# 467444_130_3_4-A.net
KiCad netlist of a schematic drawn in Altium Designer
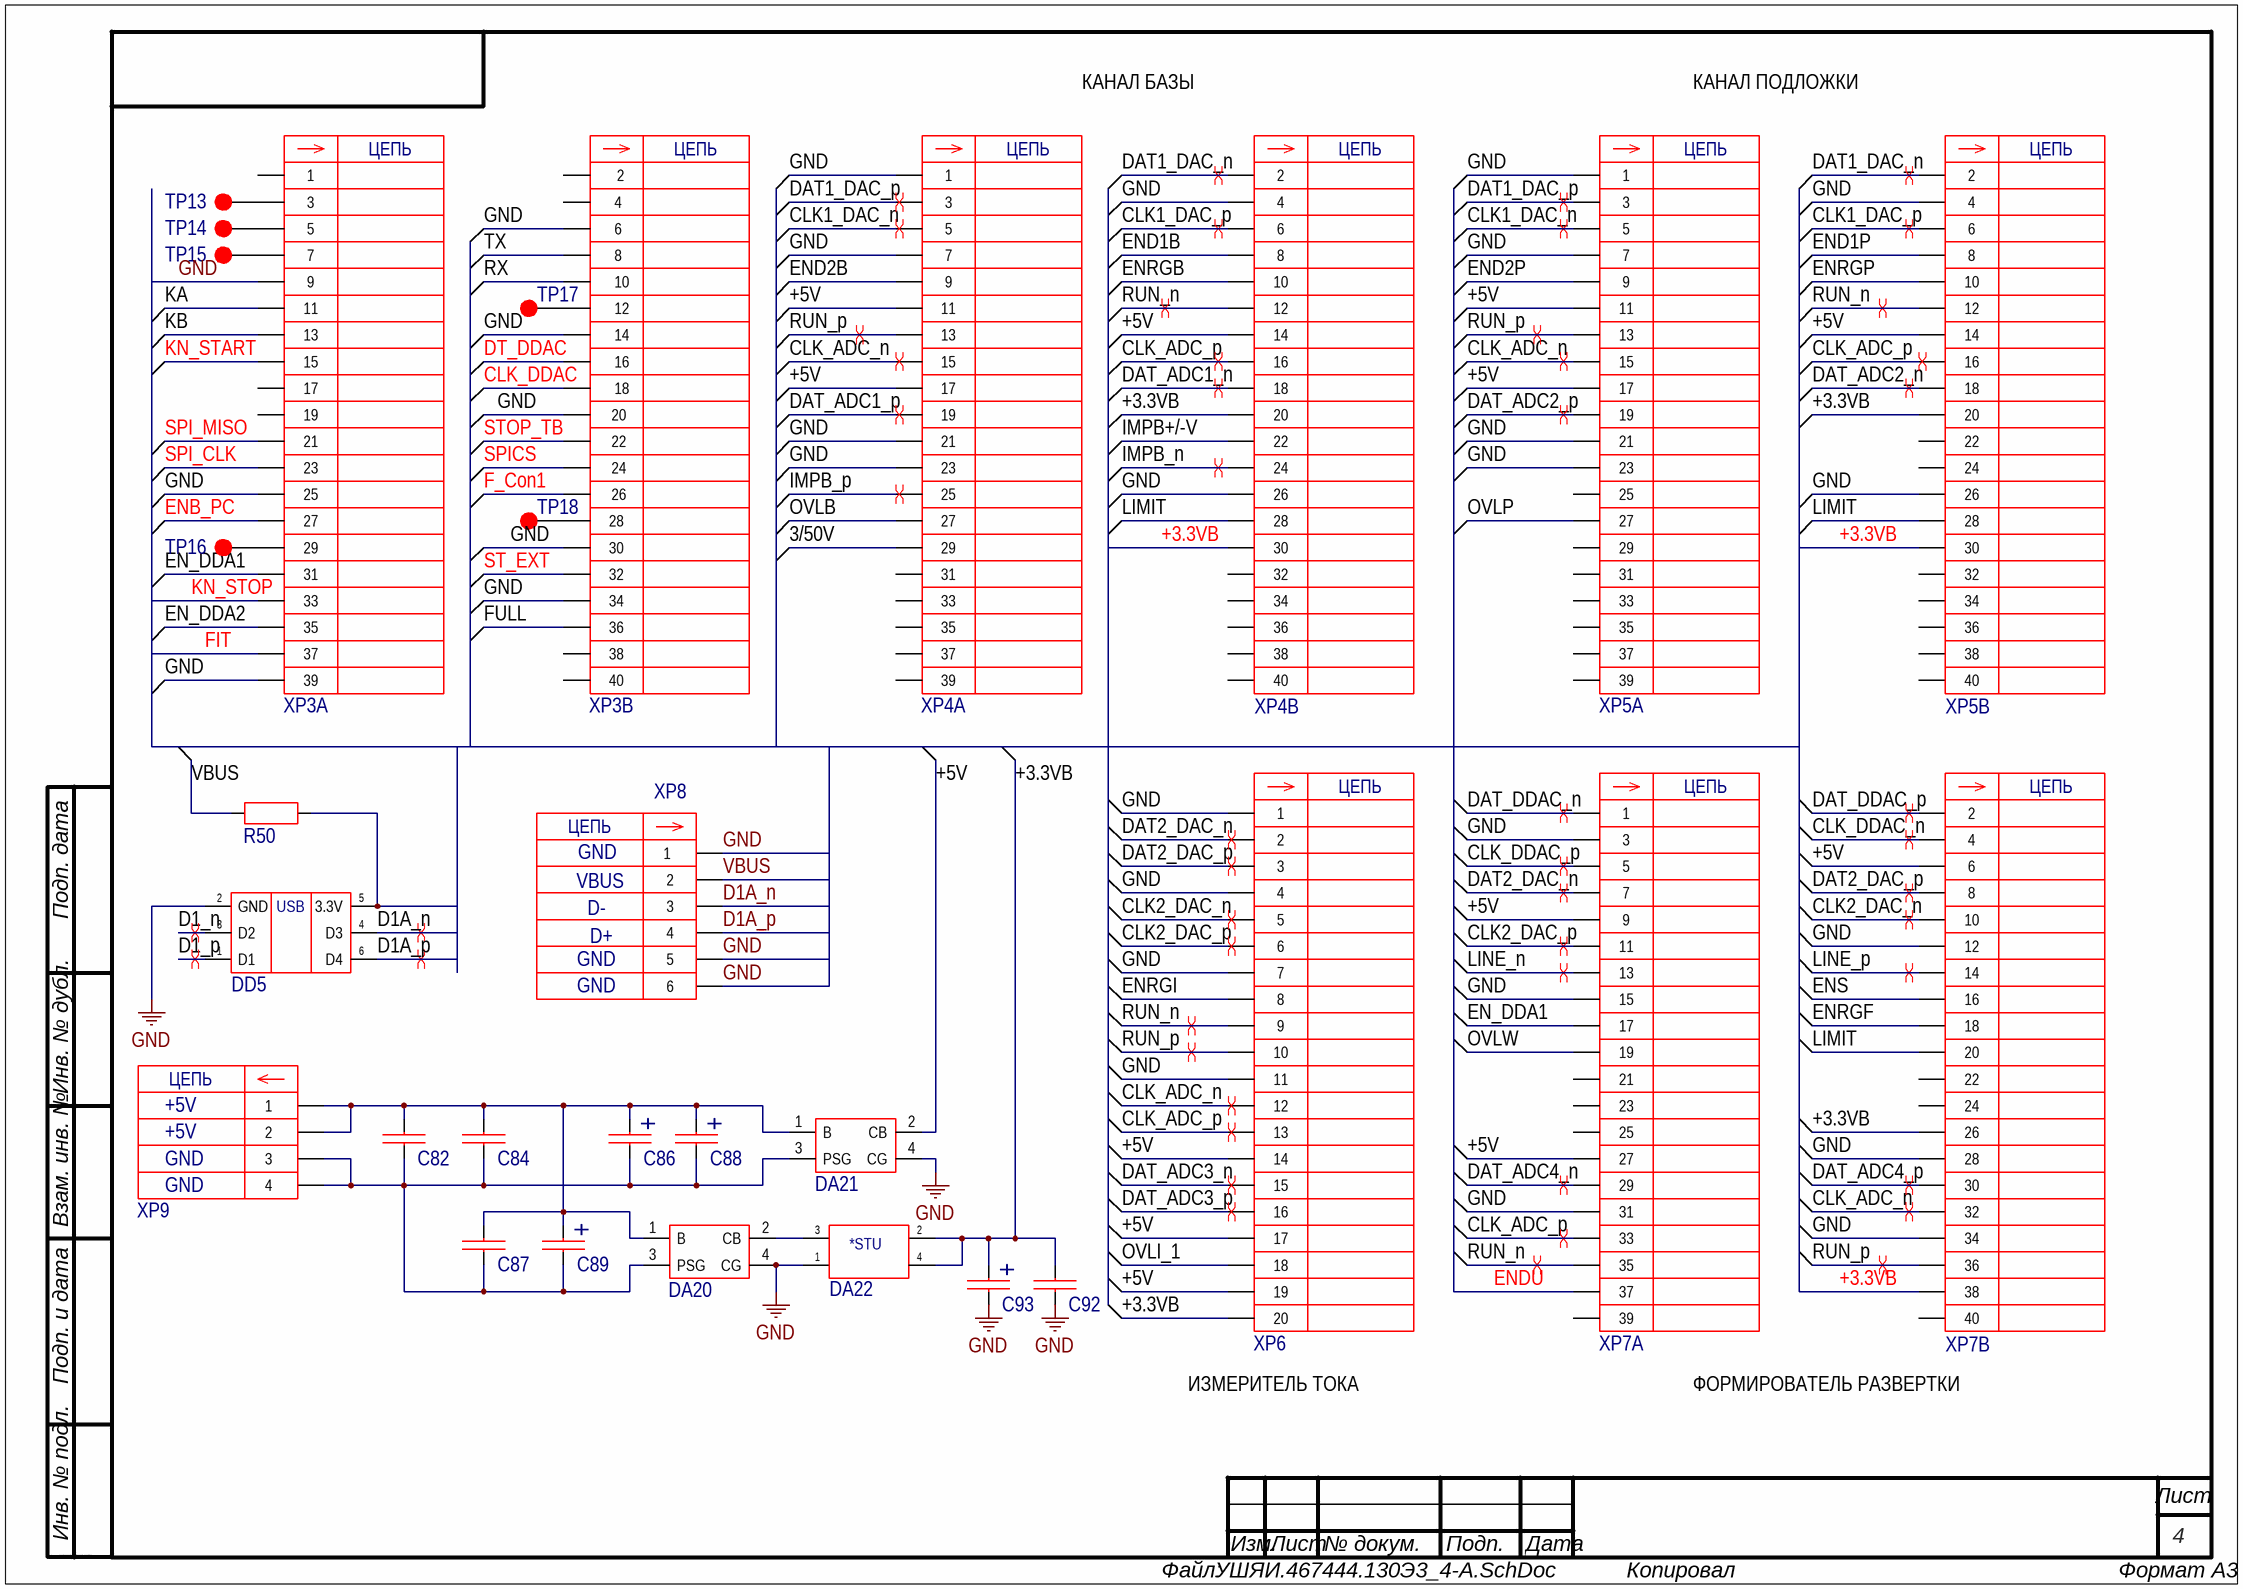
[diagram p0: УШЯИ.467444.130Э3_4-A.SchDoc]

(export (version "E")
  (design (tool "Eeschema 10.0.6"))
  (components
    (comp (ref "C82")
      (value "0,1 µF")
      (footprint "C_0805 [2012 Metric]")
      (description "Неполярный конденсатор")
      (fields (field (name "MANUFACTURER") "Murata") (field (name "VOLTAGE") "50V"))
      (libsource (lib "lib") (part "C_const"))
    )
    (comp (ref "C84")
      (value "0,1 µF")
      (footprint "C_0805 [2012 Metric]")
      (description "Неполярный конденсатор")
      (fields (field (name "MANUFACTURER") "Murata") (field (name "VOLTAGE") "50V"))
      (libsource (lib "lib") (part "C_const"))
    )
    (comp (ref "C86")
      (value "1000 µF")
      (footprint "С_EXR_10x21")
      (description "Полярный конденсатор")
      (fields (field (name "MANUFACTURER") "Hitano") (field (name "VOLTAGE") "16V"))
      (libsource (lib "lib") (part "C_electrolytic"))
    )
    (comp (ref "C87")
      (value "0,1 µF")
      (footprint "C_0805 [2012 Metric]")
      (description "Неполярный конденсатор")
      (fields (field (name "MANUFACTURER") "Murata") (field (name "VOLTAGE") "50V"))
      (libsource (lib "lib") (part "C_const"))
    )
    (comp (ref "C88")
      (value "10 µF")
      (footprint "C+_1210 [3528-21 Metric]")
      (description "Полярный конденсатор")
      (fields (field (name "MANUFACTURER") "KYOCERA AVX") (field (name "VOLTAGE") "20V\r\n10V"))
      (libsource (lib "lib") (part "C_electrolytic"))
    )
    (comp (ref "C89")
      (value "10 µF")
      (footprint "C+_1210 [3528-21 Metric]")
      (description "Полярный конденсатор")
      (fields (field (name "MANUFACTURER") "KYOCERA AVX") (field (name "VOLTAGE") "20V\r\n10V"))
      (libsource (lib "lib") (part "C_electrolytic"))
    )
    (comp (ref "C92")
      (value "0,1 µF")
      (footprint "C_0805 [2012 Metric]")
      (description "Неполярный конденсатор")
      (fields (field (name "MANUFACTURER") "Murata") (field (name "VOLTAGE") "50V"))
      (libsource (lib "lib") (part "C_const"))
    )
    (comp (ref "C93")
      (value "10 µF")
      (footprint "C+_1210 [3528-21 Metric]")
      (description "Полярный конденсатор")
      (fields (field (name "MANUFACTURER") "KYOCERA AVX") (field (name "VOLTAGE") "20V\r\n10V"))
      (libsource (lib "lib") (part "C_electrolytic"))
    )
    (comp (ref "DA20")
      (value "BNX028-01")
      (footprint "F_BNX028-01")
      (description "16В, 35дБ")
      (fields (field (name "MANUFACTURER") "Murata Electronics"))
      (libsource (lib "lib") (part "F_BNX022-01"))
    )
    (comp (ref "DA21")
      (value "BNX028-01")
      (footprint "F_BNX028-01")
      (description "16В, 35дБ")
      (fields (field (name "MANUFACTURER") "Murata Electronics"))
      (libsource (lib "lib") (part "F_BNX022-01"))
    )
    (comp (ref "DA22")
      (value "LD1117AS33TR")
      (footprint "SOT-223")
      (description "IC, Fixed LDO Voltage Regulator, 5.3V to 10V, 1.15V Dropout, 3.3Vout, 1Aout")
      (fields (field (name "MANUFACTURER") "STMicroelectronics"))
      (libsource (lib "lib") (part "VolReg_LD1117AS33TR"))
    )
    (comp (ref "DD5")
      (value "USBUF01W6")
      (footprint "SOT-323-6")
      (description "EMI Filter, 2-Channel, USB Upstream Terminator, ESD Protection")
      (fields (field (name "MANUFACTURER") "STMicroelectronics"))
      (libsource (lib "lib") (part "USBUF01W6"))
    )
    (comp (ref "R50")
      (value "30R")
      (footprint "R_0805 [2012 Metric]")
      (fields (field (name "TOLERANCE") "±5%"))
      (libsource (lib "lib") (part "R_Const"))
    )
    (comp (ref "TP13") (value "~") (footprint "DSP_1.3") (libsource (lib "lib") (part "TP")))
    (comp (ref "TP14") (value "~") (footprint "DSP_1.3") (libsource (lib "lib") (part "TP")))
    (comp (ref "TP15") (value "~") (footprint "DSP_1.3") (libsource (lib "lib") (part "TP")))
    (comp (ref "TP16") (value "~") (footprint "DSP_1.3") (libsource (lib "lib") (part "TP")))
    (comp (ref "TP17") (value "~") (footprint "DSP_1.3") (libsource (lib "lib") (part "TP")))
    (comp (ref "TP18") (value "~") (footprint "DSP_1.3") (libsource (lib "lib") (part "TP")))
    (comp (ref "XP3")
      (value "BH-40")
      (footprint "BH-40")
      (description "Male, 40 pins, 2 rows, Vertical")
      (fields (field (name "MANUFACTURER") "Connfly electronic"))
      (libsource (lib "lib") (part "M_40"))
    )
    (comp (ref "XP4")
      (value "BH2-40")
      (footprint "BH2-40")
      (description "Male, 40 pins, 2 rows, Vertical, DS1014-40, 2 mm")
      (fields (field (name "MANUFACTURER") "Connfly electronic"))
      (libsource (lib "lib") (part "M_40"))
    )
    (comp (ref "XP5")
      (value "BH2-40")
      (footprint "BH2-40")
      (description "Male, 40 pins, 2 rows, Vertical, DS1014-40, 2 mm")
      (fields (field (name "MANUFACTURER") "Connfly electronic"))
      (libsource (lib "lib") (part "M_40"))
    )
    (comp (ref "XP6")
      (value "BH2-20R")
      (footprint "BH2-20R")
      (description "Male, 20 pins, 2 rows, Right Angle, DS1014-20RF1B-B, 2 mm")
      (fields (field (name "MANUFACTURER") "Connfly electronic"))
      (libsource (lib "lib") (part "M_20"))
    )
    (comp (ref "XP7")
      (value "BH2-40")
      (footprint "BH2-40")
      (description "Male, 40 pins, 2 rows, Vertical, DS1014-40, 2 mm")
      (fields (field (name "MANUFACTURER") "Connfly electronic"))
      (libsource (lib "lib") (part "M_40"))
    )
    (comp (ref "XP8")
      (value "AMPMODU II 280372-2")
      (footprint "AMP II-280372-2")
      (description "Male, 6 pin, 1 row, Vertical, Board-to-Board, 2.54 mm")
      (fields (field (name "MANUFACTURER") "TE Connectivity"))
      (libsource (lib "Lib_MN") (part "M_6"))
    )
    (comp (ref "XP9")
      (value "AMPMODU II 280371-2")
      (footprint "AMP II-280371-2")
      (description "Male, 4 pin, 1 row, Vertical, Board-to-Board, 2.54 mm")
      (fields (field (name "MANUFACTURER") "TE Connectivity"))
      (libsource (lib "lib") (part "M_4"))
    )
  )
  (nets
    (net (code "1") (name "/+3.3VB") (class "Default")
      (node (ref "C92") (pin "2") (pinfunction "2_2") (pintype "passive"))
      (node (ref "C93") (pin "+") (pinfunction "+_+") (pintype "passive"))
      (node (ref "DA22") (pin "2") (pinfunction "VOUT_2") (pintype "passive"))
      (node (ref "DA22") (pin "4") (pinfunction "VOUT_4") (pintype "passive"))
      (node (ref "XP4") (pin "20") (pinfunction "20_20") (pintype "passive"))
      (node (ref "XP4") (pin "30") (pinfunction "30_30") (pintype "passive"))
      (node (ref "XP5") (pin "20") (pinfunction "20_20") (pintype "passive"))
      (node (ref "XP5") (pin "30") (pinfunction "30_30") (pintype "passive"))
      (node (ref "XP6") (pin "20") (pinfunction "20_20") (pintype "passive"))
      (node (ref "XP7") (pin "26") (pinfunction "26_26") (pintype "passive"))
      (node (ref "XP7") (pin "38") (pinfunction "38_38") (pintype "passive"))
    )
    (net (code "2") (name "/+5V") (class "Default")
      (node (ref "DA21") (pin "2") (pinfunction "CB_2") (pintype "passive"))
      (node (ref "XP4") (pin "11") (pinfunction "11_11") (pintype "passive"))
      (node (ref "XP4") (pin "14") (pinfunction "14_14") (pintype "passive"))
      (node (ref "XP4") (pin "17") (pinfunction "17_17") (pintype "passive"))
      (node (ref "XP5") (pin "11") (pinfunction "11_11") (pintype "passive"))
      (node (ref "XP5") (pin "14") (pinfunction "14_14") (pintype "passive"))
      (node (ref "XP5") (pin "17") (pinfunction "17_17") (pintype "passive"))
      (node (ref "XP6") (pin "14") (pinfunction "14_14") (pintype "passive"))
      (node (ref "XP6") (pin "17") (pinfunction "17_17") (pintype "passive"))
      (node (ref "XP6") (pin "19") (pinfunction "19_19") (pintype "passive"))
      (node (ref "XP7") (pin "27") (pinfunction "27_27") (pintype "passive"))
      (node (ref "XP7") (pin "6") (pinfunction "6_6") (pintype "passive"))
      (node (ref "XP7") (pin "9") (pinfunction "9_9") (pintype "passive"))
    )
    (net (code "3") (name "/3{slash}50V") (class "Default")
      (node (ref "XP4") (pin "29") (pinfunction "29_29") (pintype "passive"))
    )
    (net (code "4") (name "/CLK1_DAC_n") (class "Default")
      (node (ref "XP4") (pin "5") (pinfunction "5_5") (pintype "passive"))
      (node (ref "XP5") (pin "5") (pinfunction "5_5") (pintype "passive"))
    )
    (net (code "5") (name "/CLK1_DAC_p") (class "Default")
      (node (ref "XP4") (pin "6") (pinfunction "6_6") (pintype "passive"))
      (node (ref "XP5") (pin "6") (pinfunction "6_6") (pintype "passive"))
    )
    (net (code "6") (name "/CLK2_DAC_n") (class "Default")
      (node (ref "XP6") (pin "5") (pinfunction "5_5") (pintype "passive"))
      (node (ref "XP7") (pin "10") (pinfunction "10_10") (pintype "passive"))
    )
    (net (code "7") (name "/CLK2_DAC_p") (class "Default")
      (node (ref "XP6") (pin "6") (pinfunction "6_6") (pintype "passive"))
      (node (ref "XP7") (pin "11") (pinfunction "11_11") (pintype "passive"))
    )
    (net (code "8") (name "/CLK_ADC_n") (class "Default")
      (node (ref "XP4") (pin "15") (pinfunction "15_15") (pintype "passive"))
      (node (ref "XP5") (pin "15") (pinfunction "15_15") (pintype "passive"))
      (node (ref "XP6") (pin "12") (pinfunction "12_12") (pintype "passive"))
      (node (ref "XP7") (pin "32") (pinfunction "32_32") (pintype "passive"))
    )
    (net (code "9") (name "/CLK_ADC_p") (class "Default")
      (node (ref "XP4") (pin "16") (pinfunction "16_16") (pintype "passive"))
      (node (ref "XP5") (pin "16") (pinfunction "16_16") (pintype "passive"))
      (node (ref "XP6") (pin "13") (pinfunction "13_13") (pintype "passive"))
      (node (ref "XP7") (pin "33") (pinfunction "33_33") (pintype "passive"))
    )
    (net (code "10") (name "/CLK_DDAC") (class "Default")
      (node (ref "XP3") (pin "18") (pinfunction "18_18") (pintype "passive"))
    )
    (net (code "11") (name "/CLK_DDAC_n") (class "Default")
      (node (ref "XP7") (pin "4") (pinfunction "4_4") (pintype "passive"))
    )
    (net (code "12") (name "/CLK_DDAC_p") (class "Default")
      (node (ref "XP7") (pin "5") (pinfunction "5_5") (pintype "passive"))
    )
    (net (code "13") (name "/D1A_n") (class "Default")
      (node (ref "DD5") (pin "4") (pinfunction "D3_4") (pintype "passive"))
      (node (ref "XP8") (pin "3") (pinfunction "3_3") (pintype "passive"))
    )
    (net (code "14") (name "/D1A_p") (class "Default")
      (node (ref "DD5") (pin "6") (pinfunction "D4_6") (pintype "passive"))
      (node (ref "XP8") (pin "4") (pinfunction "4_4") (pintype "passive"))
    )
    (net (code "15") (name "/D1_n") (class "Default")
      (node (ref "DD5") (pin "3") (pinfunction "D2_3") (pintype "passive"))
    )
    (net (code "16") (name "/D1_p") (class "Default")
      (node (ref "DD5") (pin "1") (pinfunction "D1_1") (pintype "passive"))
    )
    (net (code "17") (name "/DAT1_DAC_n") (class "Default")
      (node (ref "XP4") (pin "2") (pinfunction "2_2") (pintype "passive"))
      (node (ref "XP5") (pin "2") (pinfunction "2_2") (pintype "passive"))
    )
    (net (code "18") (name "/DAT1_DAC_p") (class "Default")
      (node (ref "XP4") (pin "3") (pinfunction "3_3") (pintype "passive"))
      (node (ref "XP5") (pin "3") (pinfunction "3_3") (pintype "passive"))
    )
    (net (code "19") (name "/DAT2_DAC_n") (class "Default")
      (node (ref "XP6") (pin "2") (pinfunction "2_2") (pintype "passive"))
      (node (ref "XP7") (pin "7") (pinfunction "7_7") (pintype "passive"))
    )
    (net (code "20") (name "/DAT2_DAC_p") (class "Default")
      (node (ref "XP6") (pin "3") (pinfunction "3_3") (pintype "passive"))
      (node (ref "XP7") (pin "8") (pinfunction "8_8") (pintype "passive"))
    )
    (net (code "21") (name "/DAT_ADC1_n") (class "Default")
      (node (ref "XP4") (pin "18") (pinfunction "18_18") (pintype "passive"))
    )
    (net (code "22") (name "/DAT_ADC1_p") (class "Default")
      (node (ref "XP4") (pin "19") (pinfunction "19_19") (pintype "passive"))
    )
    (net (code "23") (name "/DAT_ADC2_n") (class "Default")
      (node (ref "XP5") (pin "18") (pinfunction "18_18") (pintype "passive"))
    )
    (net (code "24") (name "/DAT_ADC2_p") (class "Default")
      (node (ref "XP5") (pin "19") (pinfunction "19_19") (pintype "passive"))
    )
    (net (code "25") (name "/DAT_ADC3_n") (class "Default")
      (node (ref "XP6") (pin "15") (pinfunction "15_15") (pintype "passive"))
    )
    (net (code "26") (name "/DAT_ADC3_p") (class "Default")
      (node (ref "XP6") (pin "16") (pinfunction "16_16") (pintype "passive"))
    )
    (net (code "27") (name "/DAT_ADC4_n") (class "Default")
      (node (ref "XP7") (pin "29") (pinfunction "29_29") (pintype "passive"))
    )
    (net (code "28") (name "/DAT_ADC4_p") (class "Default")
      (node (ref "XP7") (pin "30") (pinfunction "30_30") (pintype "passive"))
    )
    (net (code "29") (name "/DAT_DDAC_n") (class "Default")
      (node (ref "XP7") (pin "1") (pinfunction "1_1") (pintype "passive"))
    )
    (net (code "30") (name "/DAT_DDAC_p") (class "Default")
      (node (ref "XP7") (pin "2") (pinfunction "2_2") (pintype "passive"))
    )
    (net (code "31") (name "/DT_DDAC") (class "Default")
      (node (ref "XP3") (pin "16") (pinfunction "16_16") (pintype "passive"))
    )
    (net (code "32") (name "/ENB_PC") (class "Default")
      (node (ref "XP3") (pin "27") (pinfunction "27_27") (pintype "passive"))
    )
    (net (code "33") (name "/END1B") (class "Default")
      (node (ref "XP4") (pin "8") (pinfunction "8_8") (pintype "passive"))
    )
    (net (code "34") (name "/END1P") (class "Default")
      (node (ref "XP5") (pin "8") (pinfunction "8_8") (pintype "passive"))
    )
    (net (code "35") (name "/END2B") (class "Default")
      (node (ref "XP4") (pin "9") (pinfunction "9_9") (pintype "passive"))
    )
    (net (code "36") (name "/END2P") (class "Default")
      (node (ref "XP5") (pin "9") (pinfunction "9_9") (pintype "passive"))
    )
    (net (code "37") (name "/ENDU") (class "Default")
      (node (ref "XP7") (pin "37") (pinfunction "37_37") (pintype "passive"))
    )
    (net (code "38") (name "/ENRGB") (class "Default")
      (node (ref "XP4") (pin "10") (pinfunction "10_10") (pintype "passive"))
    )
    (net (code "39") (name "/ENRGF") (class "Default")
      (node (ref "XP7") (pin "18") (pinfunction "18_18") (pintype "passive"))
    )
    (net (code "40") (name "/ENRGI") (class "Default")
      (node (ref "XP6") (pin "8") (pinfunction "8_8") (pintype "passive"))
    )
    (net (code "41") (name "/ENRGP") (class "Default")
      (node (ref "XP5") (pin "10") (pinfunction "10_10") (pintype "passive"))
    )
    (net (code "42") (name "/ENS") (class "Default")
      (node (ref "XP7") (pin "16") (pinfunction "16_16") (pintype "passive"))
    )
    (net (code "43") (name "/EN_DDA1") (class "Default")
      (node (ref "XP3") (pin "31") (pinfunction "31_31") (pintype "passive"))
      (node (ref "XP7") (pin "17") (pinfunction "17_17") (pintype "passive"))
    )
    (net (code "44") (name "/EN_DDA2") (class "Default")
      (node (ref "XP3") (pin "35") (pinfunction "35_35") (pintype "passive"))
    )
    (net (code "45") (name "/FIT") (class "Default")
      (node (ref "XP3") (pin "37") (pinfunction "37_37") (pintype "passive"))
    )
    (net (code "46") (name "/FULL") (class "Default")
      (node (ref "XP3") (pin "36") (pinfunction "36_36") (pintype "passive"))
    )
    (net (code "47") (name "/F_Con1") (class "Default")
      (node (ref "XP3") (pin "26") (pinfunction "26_26") (pintype "passive"))
    )
    (net (code "48") (name "/IMPB+{slash}-V") (class "Default")
      (node (ref "XP4") (pin "22") (pinfunction "22_22") (pintype "passive"))
    )
    (net (code "49") (name "/IMPB_n") (class "Default")
      (node (ref "XP4") (pin "24") (pinfunction "24_24") (pintype "passive"))
    )
    (net (code "50") (name "/IMPB_p") (class "Default")
      (node (ref "XP4") (pin "25") (pinfunction "25_25") (pintype "passive"))
    )
    (net (code "51") (name "/KA") (class "Default")
      (node (ref "XP3") (pin "11") (pinfunction "11_11") (pintype "passive"))
    )
    (net (code "52") (name "/KB") (class "Default")
      (node (ref "XP3") (pin "13") (pinfunction "13_13") (pintype "passive"))
    )
    (net (code "53") (name "/KN_START") (class "Default")
      (node (ref "XP3") (pin "15") (pinfunction "15_15") (pintype "passive"))
    )
    (net (code "54") (name "/KN_STOP") (class "Default")
      (node (ref "XP3") (pin "33") (pinfunction "33_33") (pintype "passive"))
    )
    (net (code "55") (name "/LIMIT") (class "Default")
      (node (ref "XP4") (pin "28") (pinfunction "28_28") (pintype "passive"))
      (node (ref "XP5") (pin "28") (pinfunction "28_28") (pintype "passive"))
      (node (ref "XP7") (pin "20") (pinfunction "20_20") (pintype "passive"))
    )
    (net (code "56") (name "/LINE_n") (class "Default")
      (node (ref "XP7") (pin "13") (pinfunction "13_13") (pintype "passive"))
    )
    (net (code "57") (name "/LINE_p") (class "Default")
      (node (ref "XP7") (pin "14") (pinfunction "14_14") (pintype "passive"))
    )
    (net (code "58") (name "/OVLB") (class "Default")
      (node (ref "XP4") (pin "27") (pinfunction "27_27") (pintype "passive"))
    )
    (net (code "59") (name "/OVLI_1") (class "Default")
      (node (ref "XP6") (pin "18") (pinfunction "18_18") (pintype "passive"))
    )
    (net (code "60") (name "/OVLP") (class "Default")
      (node (ref "XP5") (pin "27") (pinfunction "27_27") (pintype "passive"))
    )
    (net (code "61") (name "/OVLW") (class "Default")
      (node (ref "XP7") (pin "19") (pinfunction "19_19") (pintype "passive"))
    )
    (net (code "62") (name "/RUN_n") (class "Default")
      (node (ref "XP4") (pin "12") (pinfunction "12_12") (pintype "passive"))
      (node (ref "XP5") (pin "12") (pinfunction "12_12") (pintype "passive"))
      (node (ref "XP6") (pin "9") (pinfunction "9_9") (pintype "passive"))
      (node (ref "XP7") (pin "35") (pinfunction "35_35") (pintype "passive"))
    )
    (net (code "63") (name "/RUN_p") (class "Default")
      (node (ref "XP4") (pin "13") (pinfunction "13_13") (pintype "passive"))
      (node (ref "XP5") (pin "13") (pinfunction "13_13") (pintype "passive"))
      (node (ref "XP6") (pin "10") (pinfunction "10_10") (pintype "passive"))
      (node (ref "XP7") (pin "36") (pinfunction "36_36") (pintype "passive"))
    )
    (net (code "64") (name "/RX") (class "Default")
      (node (ref "XP3") (pin "10") (pinfunction "10_10") (pintype "passive"))
    )
    (net (code "65") (name "/SPICS") (class "Default")
      (node (ref "XP3") (pin "24") (pinfunction "24_24") (pintype "passive"))
    )
    (net (code "66") (name "/SPI_CLK") (class "Default")
      (node (ref "XP3") (pin "23") (pinfunction "23_23") (pintype "passive"))
    )
    (net (code "67") (name "/SPI_MISO") (class "Default")
      (node (ref "XP3") (pin "21") (pinfunction "21_21") (pintype "passive"))
    )
    (net (code "68") (name "/STOP_TB") (class "Default")
      (node (ref "XP3") (pin "22") (pinfunction "22_22") (pintype "passive"))
    )
    (net (code "69") (name "/ST_EXT") (class "Default")
      (node (ref "XP3") (pin "32") (pinfunction "32_32") (pintype "passive"))
    )
    (net (code "70") (name "/TX") (class "Default")
      (node (ref "XP3") (pin "8") (pinfunction "8_8") (pintype "passive"))
    )
    (net (code "71") (name "/VBUS") (class "Default")
      (node (ref "R50") (pin "1") (pinfunction "1_1") (pintype "passive"))
      (node (ref "XP8") (pin "2") (pinfunction "2_2") (pintype "passive"))
    )
    (net (code "72") (name "GND") (class "Default")
      (node (ref "C92") (pin "1") (pinfunction "1_1") (pintype "passive"))
      (node (ref "C93") (pin "-") (pinfunction "-_-") (pintype "passive"))
      (node (ref "DA20") (pin "4") (pinfunction "CG_4") (pintype "passive"))
      (node (ref "DA21") (pin "4") (pinfunction "CG_4") (pintype "passive"))
      (node (ref "DA22") (pin "1") (pinfunction "ADJ/GND_1") (pintype "passive"))
      (node (ref "DD5") (pin "2") (pinfunction "GND_2") (pintype "passive"))
      (node (ref "XP3") (pin "14") (pinfunction "14_14") (pintype "passive"))
      (node (ref "XP3") (pin "20") (pinfunction "20_20") (pintype "passive"))
      (node (ref "XP3") (pin "25") (pinfunction "25_25") (pintype "passive"))
      (node (ref "XP3") (pin "30") (pinfunction "30_30") (pintype "passive"))
      (node (ref "XP3") (pin "34") (pinfunction "34_34") (pintype "passive"))
      (node (ref "XP3") (pin "39") (pinfunction "39_39") (pintype "passive"))
      (node (ref "XP3") (pin "6") (pinfunction "6_6") (pintype "passive"))
      (node (ref "XP3") (pin "9") (pinfunction "9_9") (pintype "passive"))
      (node (ref "XP4") (pin "1") (pinfunction "1_1") (pintype "passive"))
      (node (ref "XP4") (pin "21") (pinfunction "21_21") (pintype "passive"))
      (node (ref "XP4") (pin "23") (pinfunction "23_23") (pintype "passive"))
      (node (ref "XP4") (pin "26") (pinfunction "26_26") (pintype "passive"))
      (node (ref "XP4") (pin "4") (pinfunction "4_4") (pintype "passive"))
      (node (ref "XP4") (pin "7") (pinfunction "7_7") (pintype "passive"))
      (node (ref "XP5") (pin "1") (pinfunction "1_1") (pintype "passive"))
      (node (ref "XP5") (pin "21") (pinfunction "21_21") (pintype "passive"))
      (node (ref "XP5") (pin "23") (pinfunction "23_23") (pintype "passive"))
      (node (ref "XP5") (pin "26") (pinfunction "26_26") (pintype "passive"))
      (node (ref "XP5") (pin "4") (pinfunction "4_4") (pintype "passive"))
      (node (ref "XP5") (pin "7") (pinfunction "7_7") (pintype "passive"))
      (node (ref "XP6") (pin "1") (pinfunction "1_1") (pintype "passive"))
      (node (ref "XP6") (pin "11") (pinfunction "11_11") (pintype "passive"))
      (node (ref "XP6") (pin "4") (pinfunction "4_4") (pintype "passive"))
      (node (ref "XP6") (pin "7") (pinfunction "7_7") (pintype "passive"))
      (node (ref "XP7") (pin "12") (pinfunction "12_12") (pintype "passive"))
      (node (ref "XP7") (pin "15") (pinfunction "15_15") (pintype "passive"))
      (node (ref "XP7") (pin "28") (pinfunction "28_28") (pintype "passive"))
      (node (ref "XP7") (pin "3") (pinfunction "3_3") (pintype "passive"))
      (node (ref "XP7") (pin "31") (pinfunction "31_31") (pintype "passive"))
      (node (ref "XP7") (pin "34") (pinfunction "34_34") (pintype "passive"))
      (node (ref "XP8") (pin "1") (pinfunction "1_1") (pintype "passive"))
      (node (ref "XP8") (pin "5") (pinfunction "5_5") (pintype "passive"))
      (node (ref "XP8") (pin "6") (pinfunction "6_6") (pintype "passive"))
    )
    (net (code "73") (name "Net-(DA20-B)") (class "Default")
      (node (ref "C82") (pin "1") (pinfunction "1_1") (pintype "passive"))
      (node (ref "C84") (pin "1") (pinfunction "1_1") (pintype "passive"))
      (node (ref "C86") (pin "+") (pinfunction "+_+") (pintype "passive"))
      (node (ref "C87") (pin "2") (pinfunction "2_2") (pintype "passive"))
      (node (ref "C88") (pin "+") (pinfunction "+_+") (pintype "passive"))
      (node (ref "C89") (pin "+") (pinfunction "+_+") (pintype "passive"))
      (node (ref "DA20") (pin "1") (pinfunction "B_1") (pintype "passive"))
      (node (ref "DA21") (pin "1") (pinfunction "B_1") (pintype "passive"))
      (node (ref "XP9") (pin "1") (pinfunction "1_1") (pintype "passive"))
      (node (ref "XP9") (pin "2") (pinfunction "2_2") (pintype "passive"))
    )
    (net (code "74") (name "Net-(DA20-CB)") (class "Default")
      (node (ref "DA20") (pin "2") (pinfunction "CB_2") (pintype "passive"))
      (node (ref "DA22") (pin "3") (pinfunction "VIN_3") (pintype "passive"))
    )
    (net (code "75") (name "Net-(DA20-PSG)") (class "Default")
      (node (ref "C82") (pin "2") (pinfunction "2_2") (pintype "passive"))
      (node (ref "C84") (pin "2") (pinfunction "2_2") (pintype "passive"))
      (node (ref "C86") (pin "-") (pinfunction "-_-") (pintype "passive"))
      (node (ref "C87") (pin "1") (pinfunction "1_1") (pintype "passive"))
      (node (ref "C88") (pin "-") (pinfunction "-_-") (pintype "passive"))
      (node (ref "C89") (pin "-") (pinfunction "-_-") (pintype "passive"))
      (node (ref "DA20") (pin "3") (pinfunction "PSG_3") (pintype "passive"))
      (node (ref "DA21") (pin "3") (pinfunction "PSG_3") (pintype "passive"))
      (node (ref "XP9") (pin "3") (pinfunction "3_3") (pintype "passive"))
      (node (ref "XP9") (pin "4") (pinfunction "4_4") (pintype "passive"))
    )
    (net (code "76") (name "Net-(DD5-3.3V)") (class "Default")
      (node (ref "DD5") (pin "5") (pinfunction "3.3V_5") (pintype "passive"))
      (node (ref "R50") (pin "2") (pinfunction "2_2") (pintype "passive"))
    )
    (net (code "77") (name "Net-(TP13-Pad1)") (class "Default")
      (node (ref "TP13") (pin "1") (pinfunction "1_1") (pintype "passive"))
      (node (ref "XP3") (pin "3") (pinfunction "3_3") (pintype "passive"))
    )
    (net (code "78") (name "Net-(TP14-Pad1)") (class "Default")
      (node (ref "TP14") (pin "1") (pinfunction "1_1") (pintype "passive"))
      (node (ref "XP3") (pin "5") (pinfunction "5_5") (pintype "passive"))
    )
    (net (code "79") (name "Net-(TP15-Pad1)") (class "Default")
      (node (ref "TP15") (pin "1") (pinfunction "1_1") (pintype "passive"))
      (node (ref "XP3") (pin "7") (pinfunction "7_7") (pintype "passive"))
    )
    (net (code "80") (name "Net-(TP16-Pad1)") (class "Default")
      (node (ref "TP16") (pin "1") (pinfunction "1_1") (pintype "passive"))
      (node (ref "XP3") (pin "29") (pinfunction "29_29") (pintype "passive"))
    )
    (net (code "81") (name "Net-(TP17-Pad1)") (class "Default")
      (node (ref "TP17") (pin "1") (pinfunction "1_1") (pintype "passive"))
      (node (ref "XP3") (pin "12") (pinfunction "12_12") (pintype "passive"))
    )
    (net (code "82") (name "Net-(TP18-Pad1)") (class "Default")
      (node (ref "TP18") (pin "1") (pinfunction "1_1") (pintype "passive"))
      (node (ref "XP3") (pin "28") (pinfunction "28_28") (pintype "passive"))
    )
    (net (code "83") (name "unconnected-(XP3-Pad1)") (class "Default")
      (node (ref "XP3") (pin "1") (pinfunction "1_1") (pintype "passive"))
    )
    (net (code "84") (name "unconnected-(XP3-Pad2)") (class "Default")
      (node (ref "XP3") (pin "2") (pinfunction "2_2") (pintype "passive"))
    )
    (net (code "85") (name "unconnected-(XP3-Pad4)") (class "Default")
      (node (ref "XP3") (pin "4") (pinfunction "4_4") (pintype "passive"))
    )
    (net (code "86") (name "unconnected-(XP3-Pad17)") (class "Default")
      (node (ref "XP3") (pin "17") (pinfunction "17_17") (pintype "passive"))
    )
    (net (code "87") (name "unconnected-(XP3-Pad19)") (class "Default")
      (node (ref "XP3") (pin "19") (pinfunction "19_19") (pintype "passive"))
    )
    (net (code "88") (name "unconnected-(XP3-Pad38)") (class "Default")
      (node (ref "XP3") (pin "38") (pinfunction "38_38") (pintype "passive"))
    )
    (net (code "89") (name "unconnected-(XP3-Pad40)") (class "Default")
      (node (ref "XP3") (pin "40") (pinfunction "40_40") (pintype "passive"))
    )
    (net (code "90") (name "unconnected-(XP4-Pad31)") (class "Default")
      (node (ref "XP4") (pin "31") (pinfunction "31_31") (pintype "passive"))
    )
    (net (code "91") (name "unconnected-(XP4-Pad32)") (class "Default")
      (node (ref "XP4") (pin "32") (pinfunction "32_32") (pintype "passive"))
    )
    (net (code "92") (name "unconnected-(XP4-Pad33)") (class "Default")
      (node (ref "XP4") (pin "33") (pinfunction "33_33") (pintype "passive"))
    )
    (net (code "93") (name "unconnected-(XP4-Pad34)") (class "Default")
      (node (ref "XP4") (pin "34") (pinfunction "34_34") (pintype "passive"))
    )
    (net (code "94") (name "unconnected-(XP4-Pad35)") (class "Default")
      (node (ref "XP4") (pin "35") (pinfunction "35_35") (pintype "passive"))
    )
    (net (code "95") (name "unconnected-(XP4-Pad36)") (class "Default")
      (node (ref "XP4") (pin "36") (pinfunction "36_36") (pintype "passive"))
    )
    (net (code "96") (name "unconnected-(XP4-Pad37)") (class "Default")
      (node (ref "XP4") (pin "37") (pinfunction "37_37") (pintype "passive"))
    )
    (net (code "97") (name "unconnected-(XP4-Pad38)") (class "Default")
      (node (ref "XP4") (pin "38") (pinfunction "38_38") (pintype "passive"))
    )
    (net (code "98") (name "unconnected-(XP4-Pad39)") (class "Default")
      (node (ref "XP4") (pin "39") (pinfunction "39_39") (pintype "passive"))
    )
    (net (code "99") (name "unconnected-(XP4-Pad40)") (class "Default")
      (node (ref "XP4") (pin "40") (pinfunction "40_40") (pintype "passive"))
    )
    (net (code "100") (name "unconnected-(XP5-Pad22)") (class "Default")
      (node (ref "XP5") (pin "22") (pinfunction "22_22") (pintype "passive"))
    )
    (net (code "101") (name "unconnected-(XP5-Pad24)") (class "Default")
      (node (ref "XP5") (pin "24") (pinfunction "24_24") (pintype "passive"))
    )
    (net (code "102") (name "unconnected-(XP5-Pad25)") (class "Default")
      (node (ref "XP5") (pin "25") (pinfunction "25_25") (pintype "passive"))
    )
    (net (code "103") (name "unconnected-(XP5-Pad29)") (class "Default")
      (node (ref "XP5") (pin "29") (pinfunction "29_29") (pintype "passive"))
    )
    (net (code "104") (name "unconnected-(XP5-Pad31)") (class "Default")
      (node (ref "XP5") (pin "31") (pinfunction "31_31") (pintype "passive"))
    )
    (net (code "105") (name "unconnected-(XP5-Pad32)") (class "Default")
      (node (ref "XP5") (pin "32") (pinfunction "32_32") (pintype "passive"))
    )
    (net (code "106") (name "unconnected-(XP5-Pad33)") (class "Default")
      (node (ref "XP5") (pin "33") (pinfunction "33_33") (pintype "passive"))
    )
    (net (code "107") (name "unconnected-(XP5-Pad34)") (class "Default")
      (node (ref "XP5") (pin "34") (pinfunction "34_34") (pintype "passive"))
    )
    (net (code "108") (name "unconnected-(XP5-Pad35)") (class "Default")
      (node (ref "XP5") (pin "35") (pinfunction "35_35") (pintype "passive"))
    )
    (net (code "109") (name "unconnected-(XP5-Pad36)") (class "Default")
      (node (ref "XP5") (pin "36") (pinfunction "36_36") (pintype "passive"))
    )
    (net (code "110") (name "unconnected-(XP5-Pad37)") (class "Default")
      (node (ref "XP5") (pin "37") (pinfunction "37_37") (pintype "passive"))
    )
    (net (code "111") (name "unconnected-(XP5-Pad38)") (class "Default")
      (node (ref "XP5") (pin "38") (pinfunction "38_38") (pintype "passive"))
    )
    (net (code "112") (name "unconnected-(XP5-Pad39)") (class "Default")
      (node (ref "XP5") (pin "39") (pinfunction "39_39") (pintype "passive"))
    )
    (net (code "113") (name "unconnected-(XP5-Pad40)") (class "Default")
      (node (ref "XP5") (pin "40") (pinfunction "40_40") (pintype "passive"))
    )
    (net (code "114") (name "unconnected-(XP7-Pad21)") (class "Default")
      (node (ref "XP7") (pin "21") (pinfunction "21_21") (pintype "passive"))
    )
    (net (code "115") (name "unconnected-(XP7-Pad22)") (class "Default")
      (node (ref "XP7") (pin "22") (pinfunction "22_22") (pintype "passive"))
    )
    (net (code "116") (name "unconnected-(XP7-Pad23)") (class "Default")
      (node (ref "XP7") (pin "23") (pinfunction "23_23") (pintype "passive"))
    )
    (net (code "117") (name "unconnected-(XP7-Pad24)") (class "Default")
      (node (ref "XP7") (pin "24") (pinfunction "24_24") (pintype "passive"))
    )
    (net (code "118") (name "unconnected-(XP7-Pad25)") (class "Default")
      (node (ref "XP7") (pin "25") (pinfunction "25_25") (pintype "passive"))
    )
    (net (code "119") (name "unconnected-(XP7-Pad39)") (class "Default")
      (node (ref "XP7") (pin "39") (pinfunction "39_39") (pintype "passive"))
    )
    (net (code "120") (name "unconnected-(XP7-Pad40)") (class "Default")
      (node (ref "XP7") (pin "40") (pinfunction "40_40") (pintype "passive"))
    )
  )
)
